# H1DR11.net
KiCad netlist of a schematic drawn in EAGLE
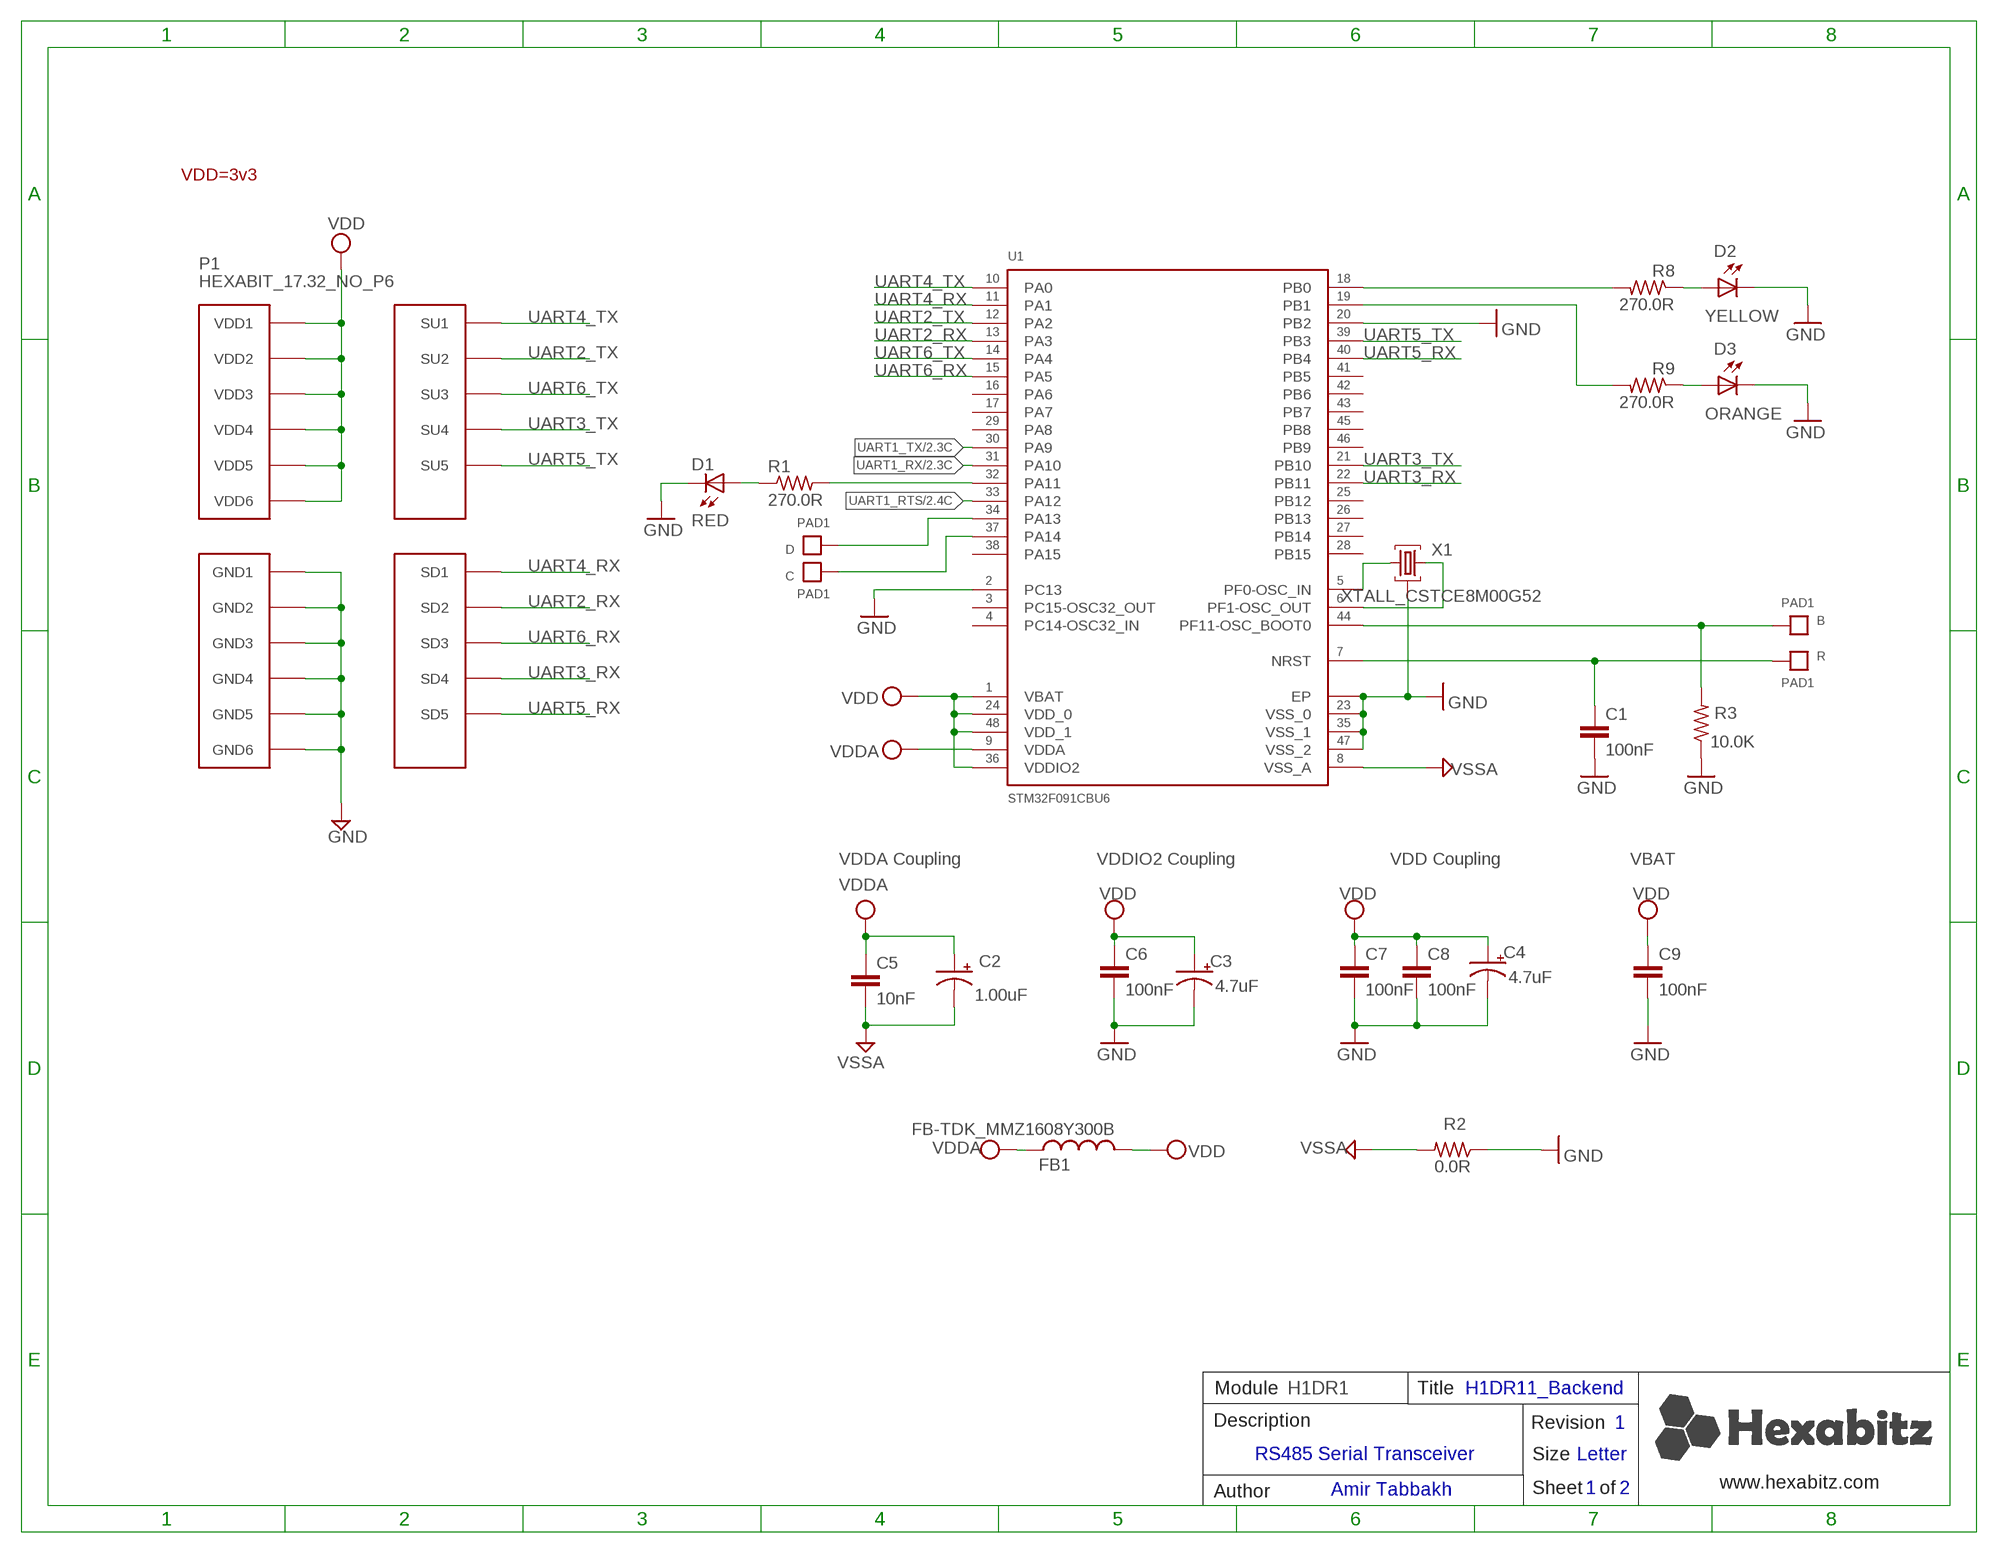
[diagram p0: schematic, sheet 1]
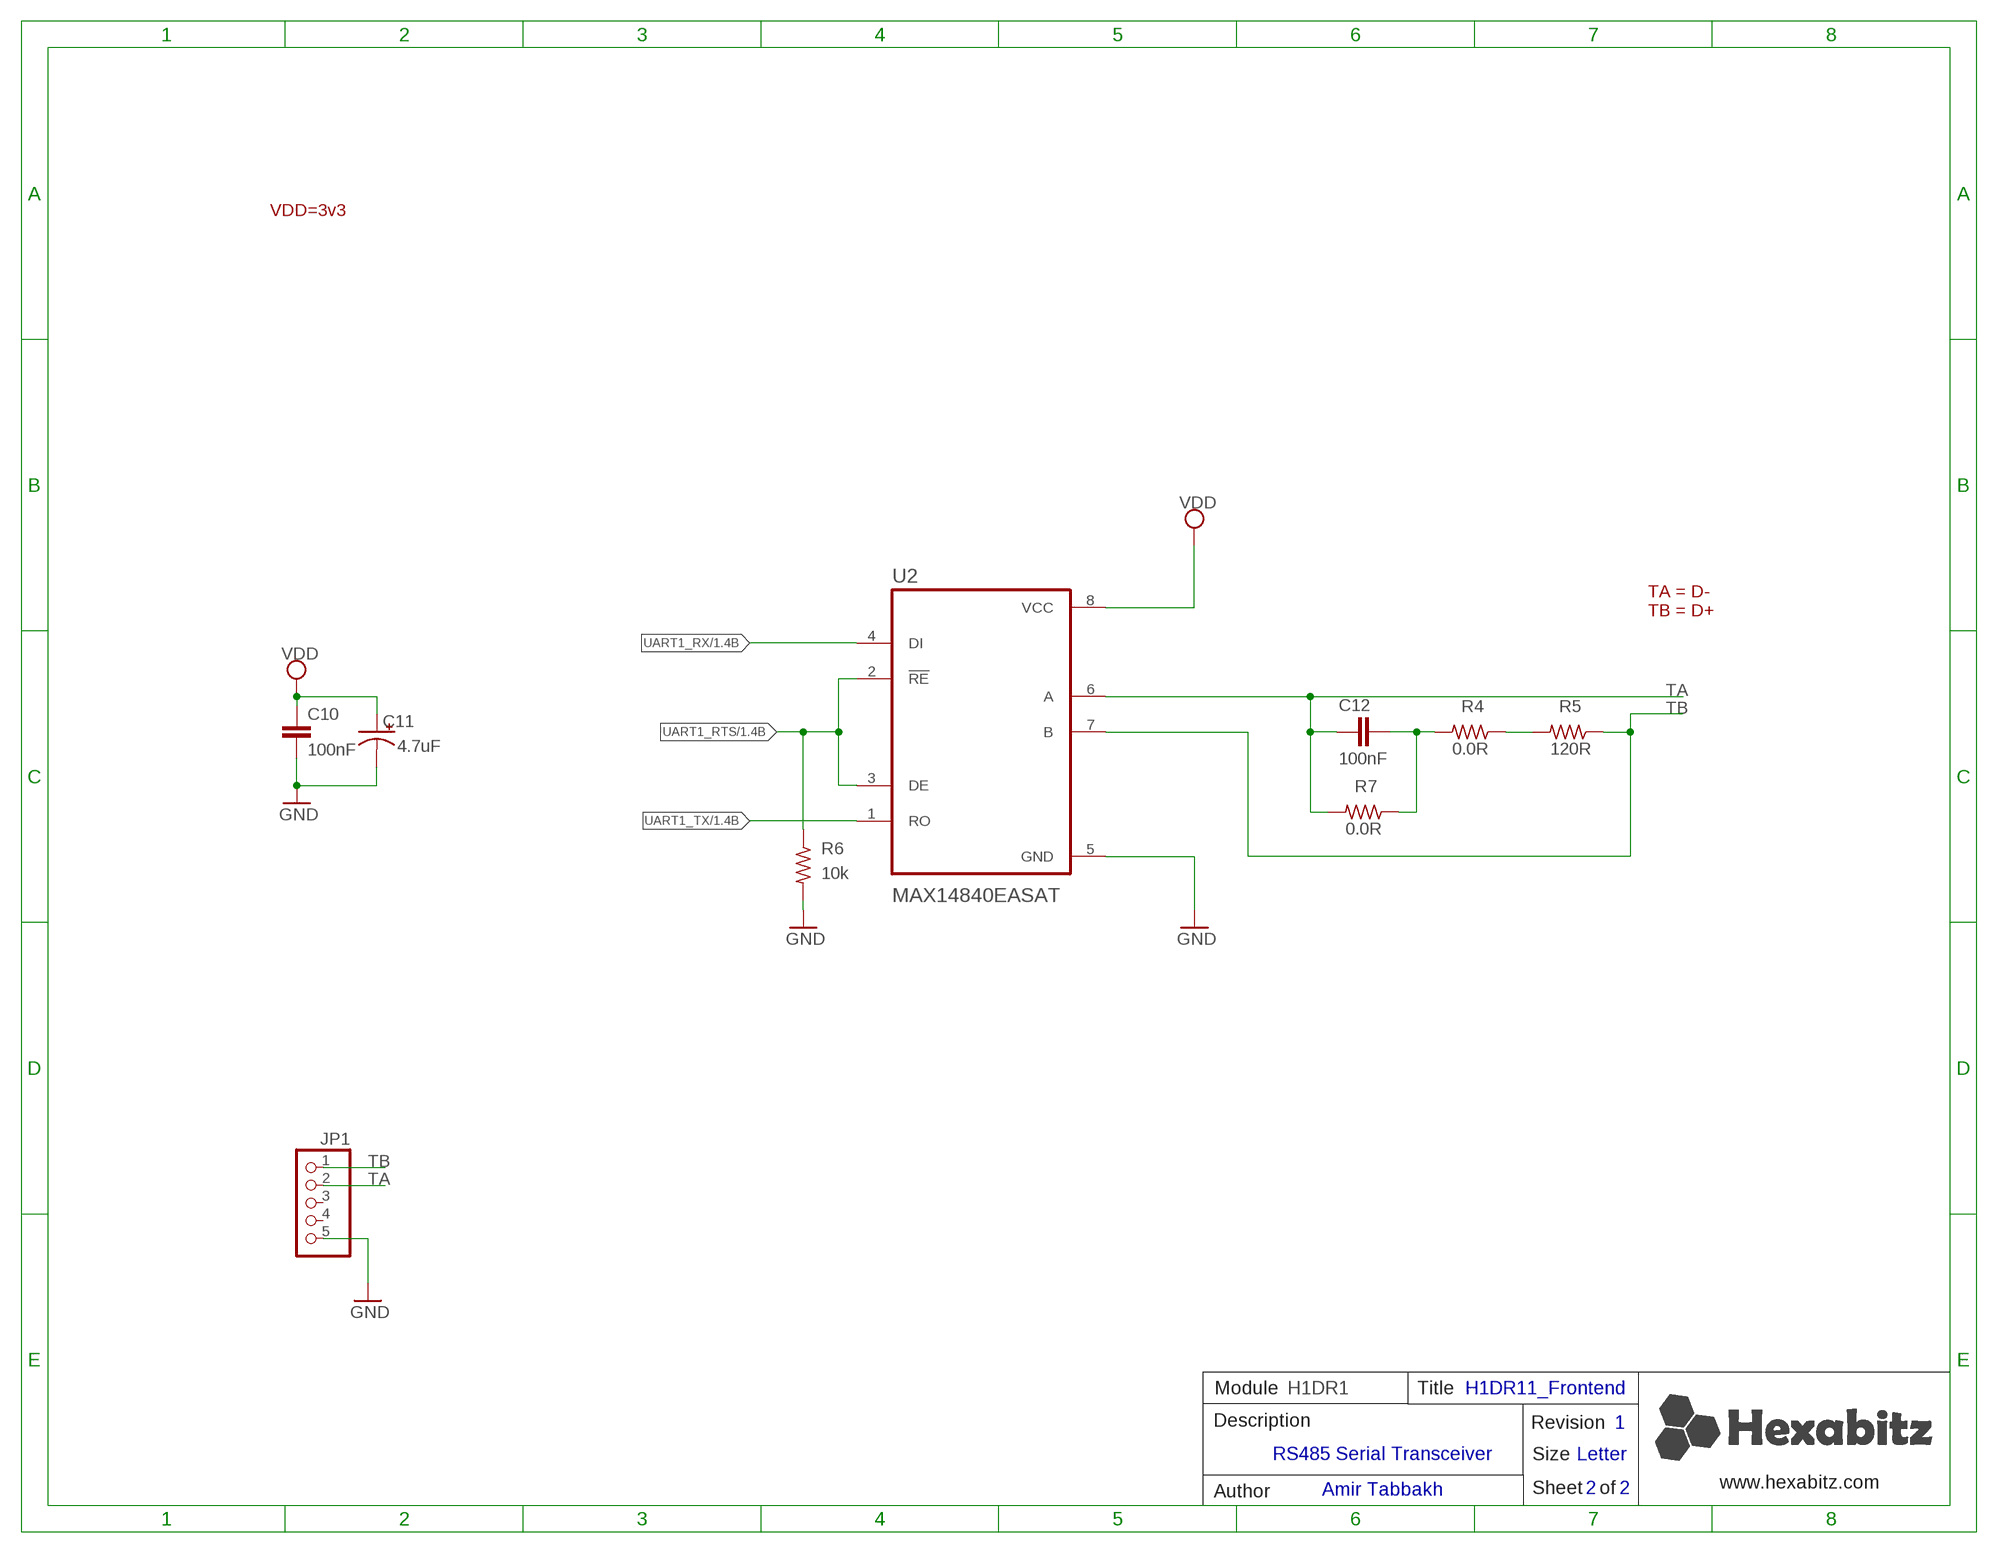
[diagram p1: schematic, sheet 2]

(export (version "E")
  (design (tool "Eeschema 10.0.6"))
  (components
    (comp (ref "C10")
      (value "100nF")
      (footprint "eagle-import:C-0603")
      (fields
        (field (name "CAPACITANCE") "100nF")
        (field (name "MFN") "KEMET")
        (field (name "MPN") "C0603C104K8RACTU")
        (field (name "OCTOPART_URL") "https://octopart.com/c0603c104k8ractu-kemet-145075?r=sp&s=9bS9ASSwSEqMCE9KBEQZ0g")
        (field (name "TOLERANCE") "10%")
        (field (name "VOLTAGE_RATING") "10V")
      )
      (libsource (lib "eagle-import") (part "C-0603"))
    )
    (comp (ref "C11")
      (value "4.7uF")
      (footprint "eagle-import:C-0805-POL")
      (fields
        (field (name "CAPACITANCE") "4.7uF")
        (field (name "MFN") "Murata")
        (field (name "MPN") "GRM21BC81E475KA12L")
        (field (name "OCTOPART_URL") "https://octopart.com/grm21bc81e475ka12l-murata-10331911?r=sp&s=RY3qZSD8T6mG6TC9CHI5qQ")
        (field (name "TOLERANCE") "10%")
        (field (name "VOLTAGE_RATING") "25V")
      )
      (libsource (lib "eagle-import") (part "C-0805-POL"))
    )
    (comp (ref "C12")
      (value "100nF")
      (footprint "eagle-import:C-0603")
      (fields
        (field (name "CAPACITANCE") "100nF")
        (field (name "MFN") "AVX")
        (field (name "MPN") "0603YC104K4T2A")
        (field (name "OCTOPART_URL") "https://octopart.com/0603yc104k4t2a-avx+interconnect+%2F+elco-8120651")
        (field (name "TOLERANCE") "10%")
        (field (name "VOLTAGE_RATING") "16V")
      )
      (libsource (lib "eagle-import") (part "C-0603"))
    )
    (comp (ref "JP1")
      (value "PINHD-1X5/90")
      (footprint "eagle-import:1X05_90")
      (description "Conn Header R/a 5POS 2.54MM MALE")
      (fields (field (name "MPN") "PEC05SBAN"))
      (libsource (lib "eagle-import") (part "PINHD-1X5/90"))
    )
    (comp (ref "R4")
      (value "0.0R")
      (footprint "eagle-import:R-0603")
      (fields
        (field (name "MFN") "Vishay")
        (field (name "MPN") "DNP")
        (field (name "OCTOPART_URL") "https://octopart.com/crcw06030000z0ea-vishay-39556096#")
        (field (name "RESISTANCE") "DNP")
      )
      (libsource (lib "eagle-import") (part "R-0603"))
    )
    (comp (ref "R5")
      (value "120R")
      (footprint "eagle-import:R-0805")
      (fields
        (field (name "MFN") "Panasonic")
        (field (name "MPN") "ERJP6WF1200V")
        (field (name "OCTOPART_URL") "https://octopart.com/erjp6wf1200v-panasonic-25949195?r=sp#")
        (field (name "RESISTANCE") "120R")
        (field (name "TOLERANCE") "1%")
      )
      (libsource (lib "eagle-import") (part "R-0805"))
    )
    (comp (ref "R6")
      (value "10k")
      (footprint "eagle-import:R-0603")
      (fields
        (field (name "MFN") "Vishay")
        (field (name "MPN") "CRCW060310K0JNEB")
        (field (name "OCTOPART_URL") "https://octopart.com/crcw060310k0jneb-vishay+dale-46603268")
        (field (name "RESISTANCE") "10k")
        (field (name "TOLERANCE") "5%")
      )
      (libsource (lib "eagle-import") (part "R-0603"))
    )
    (comp (ref "R7")
      (value "0.0R")
      (footprint "eagle-import:R-0603")
      (fields
        (field (name "MFN") "Vishay")
        (field (name "MPN") "CRCW06030000Z0EA")
        (field (name "OCTOPART_URL") "https://octopart.com/crcw06030000z0ea-vishay-39556096#")
        (field (name "RESISTANCE") "0.0 Ohm")
      )
      (libsource (lib "eagle-import") (part "R-0603"))
    )
    (comp (ref "U2")
      (value "MAX14840EASAT")
      (footprint "eagle-import:SOIC127P600X175-8N")
      (fields (field (name "MPN") "MAX14840EASA+"))
      (libsource (lib "eagle-import") (part "MAX14840EASAT"))
    )
    (comp (ref "B")
      (value "PAD1")
      (footprint "eagle-import:PAD1")
      (libsource (lib "eagle-import") (part "PAD1"))
    )
    (comp (ref "C")
      (value "PAD1")
      (footprint "eagle-import:PAD1")
      (libsource (lib "eagle-import") (part "PAD1"))
    )
    (comp (ref "C1")
      (value "100nF")
      (footprint "eagle-import:C-0603")
      (fields
        (field (name "CAPACITANCE") "100nF")
        (field (name "MFN") "KEMET")
        (field (name "MPN") "C0603C104K8RACTU")
        (field (name "OCTOPART_URL") "https://octopart.com/c0603c104k8ractu-kemet-145075?r=sp&s=9bS9ASSwSEqMCE9KBEQZ0g")
        (field (name "TOLERANCE") "10%")
        (field (name "VOLTAGE_RATING") "10V")
      )
      (libsource (lib "eagle-import") (part "C-0603"))
    )
    (comp (ref "C2")
      (value "1.00uF")
      (footprint "eagle-import:C-0805-POL")
      (fields
        (field (name "CAPACITANCE") "1.00uF")
        (field (name "MFN") "Yageo")
        (field (name "MPN") "CC0805KKX7R7BB105")
        (field (name "OCTOPART_URL") "https://octopart.com/cc0805kkx7r7bb105-yageo-8376555?r=sp&s=YKl1wwtkROau_X5nniH2ig")
        (field (name "TOLERANCE") "10%")
        (field (name "VOLTAGE_RATING") "16V")
      )
      (libsource (lib "eagle-import") (part "C-0805-POL"))
    )
    (comp (ref "C3")
      (value "4.7uF")
      (footprint "eagle-import:C-0805-POL")
      (fields
        (field (name "CAPACITANCE") "4.7uF")
        (field (name "MFN") "Murata")
        (field (name "MPN") "GRM21BC81E475KA12L")
        (field (name "OCTOPART_URL") "https://octopart.com/grm21bc81e475ka12l-murata-10331911?r=sp&s=RY3qZSD8T6mG6TC9CHI5qQ")
        (field (name "TOLERANCE") "10%")
        (field (name "VOLTAGE_RATING") "25V")
      )
      (libsource (lib "eagle-import") (part "C-0805-POL"))
    )
    (comp (ref "C4")
      (value "4.7uF")
      (footprint "eagle-import:C-0805-POL")
      (fields
        (field (name "CAPACITANCE") "4.7uF")
        (field (name "MFN") "Murata")
        (field (name "MPN") "GRM21BC81E475KA12L")
        (field (name "OCTOPART_URL") "https://octopart.com/grm21bc81e475ka12l-murata-10331911?r=sp&s=RY3qZSD8T6mG6TC9CHI5qQ")
        (field (name "TOLERANCE") "10%")
        (field (name "VOLTAGE_RATING") "25V")
      )
      (libsource (lib "eagle-import") (part "C-0805-POL"))
    )
    (comp (ref "C5")
      (value "10nF")
      (footprint "eagle-import:C-0603")
      (fields
        (field (name "CAPACITANCE") "10nF")
        (field (name "MFN") "KEMET")
        (field (name "MPN") "C0603C103K5RACTU")
        (field (name "OCTOPART_URL") "https://octopart.com/c0603c103k5ractu-kemet-133094?r=sp&s=R_iPBxLnSmGqhkU2rIMFpg")
        (field (name "TOLERANCE") "10%")
        (field (name "VOLTAGE_RATING") "50V")
      )
      (libsource (lib "eagle-import") (part "C-0603"))
    )
    (comp (ref "C6")
      (value "100nF")
      (footprint "eagle-import:C-0603")
      (fields
        (field (name "CAPACITANCE") "100nF")
        (field (name "MFN") "KEMET")
        (field (name "MPN") "C0603C104K8RACTU")
        (field (name "OCTOPART_URL") "https://octopart.com/c0603c104k8ractu-kemet-145075?r=sp&s=9bS9ASSwSEqMCE9KBEQZ0g")
        (field (name "TOLERANCE") "10%")
        (field (name "VOLTAGE_RATING") "10V")
      )
      (libsource (lib "eagle-import") (part "C-0603"))
    )
    (comp (ref "C7")
      (value "100nF")
      (footprint "eagle-import:C-0603")
      (fields
        (field (name "CAPACITANCE") "100nF")
        (field (name "MFN") "KEMET")
        (field (name "MPN") "C0603C104K8RACTU")
        (field (name "OCTOPART_URL") "https://octopart.com/c0603c104k8ractu-kemet-145075?r=sp&s=9bS9ASSwSEqMCE9KBEQZ0g")
        (field (name "TOLERANCE") "10%")
        (field (name "VOLTAGE_RATING") "10")
      )
      (libsource (lib "eagle-import") (part "C-0603"))
    )
    (comp (ref "C8")
      (value "100nF")
      (footprint "eagle-import:C-0603")
      (fields
        (field (name "CAPACITANCE") "100nF")
        (field (name "MFN") "KEMET")
        (field (name "MPN") "C0603C104K8RACTU")
        (field (name "OCTOPART_URL") "https://octopart.com/c0603c104k8ractu-kemet-145075?r=sp&s=9bS9ASSwSEqMCE9KBEQZ0g")
        (field (name "TOLERANCE") "10%")
        (field (name "VOLTAGE_RATING") "10V")
      )
      (libsource (lib "eagle-import") (part "C-0603"))
    )
    (comp (ref "C9")
      (value "100nF")
      (footprint "eagle-import:C-0603")
      (fields
        (field (name "CAPACITANCE") "100nF")
        (field (name "MFN") "KEMET")
        (field (name "MPN") "C0603C104K8RACTU")
        (field (name "OCTOPART_URL") "https://octopart.com/c0603c104k8ractu-kemet-145075?r=sp&s=9bS9ASSwSEqMCE9KBEQZ0g")
        (field (name "TOLERANCE") "10V")
        (field (name "VOLTAGE_RATING") "10%")
      )
      (libsource (lib "eagle-import") (part "C-0603"))
    )
    (comp (ref "D")
      (value "PAD1")
      (footprint "eagle-import:PAD1")
      (libsource (lib "eagle-import") (part "PAD1"))
    )
    (comp (ref "D1")
      (value "RED")
      (footprint "eagle-import:VLMS1300-GS08")
      (fields
        (field (name "MPN") "VLMS1300-GS08")
        (field (name "MFN") "Vishay")
        (field (name "MPN_1") "VLMS1300-GS08")
        (field (name "OCTOPART_URL") "https://octopart.com/vlms1300-gs08-vishay-21709201?r=sp&s=_gcP4_q8T1SC6PJQPTQ9yA")
      )
      (libsource (lib "eagle-import") (part "VLMS1300-GS08"))
    )
    (comp (ref "D2")
      (value "YELLOW")
      (footprint "eagle-import:VLMS1300-GS08")
      (fields
        (field (name "MPN") "VLMS1300-GS08")
        (field (name "MFN") "Vishay")
        (field (name "MPN_1") "VLMY1300-GS08")
        (field (name "OCTOPART_URL") "https://octopart.com/vlmy1300-gs08-vishay-21709204?r=sp")
      )
      (libsource (lib "eagle-import") (part "VLMS1300-GS08"))
    )
    (comp (ref "D3")
      (value "ORANGE")
      (footprint "eagle-import:VLMS1300-GS08")
      (fields
        (field (name "MPN") "VLMS1300-GS08")
        (field (name "MFN") "Vishay")
        (field (name "MPN_1") "VLMO1300-GS08 ")
        (field (name "OCTOPART_URL") "https://octopart.com/vlmo1300-gs08-vishay-21709200?r=sp#")
      )
      (libsource (lib "eagle-import") (part "VLMS1300-GS08"))
    )
    (comp (ref "FB1")
      (value "FB-TDK_MMZ1608Y300B")
      (footprint "eagle-import:FB-TDK_MMZ1608Y300B")
      (fields
        (field (name "MFN") "TDK ")
        (field (name "MPN") "MMZ1608Y300B")
        (field (name "OCTOPART_URL") "https://octopart.com/mmz1608y300b-tdk-368280?r=sp&s=cd9_2ZEqQ9q9UNBuQgHAiA")
      )
      (libsource (lib "eagle-import") (part "FB-TDK_MMZ1608Y300B"))
    )
    (comp (ref "P1")
      (value "HEXABIT_17.32_NO_P6")
      (footprint "eagle-import:HEXABIT_17.32_NO_P6")
      (libsource (lib "eagle-import") (part "HEXABIT_?_NO_P617.32"))
    )
    (comp (ref "R")
      (value "PAD1")
      (footprint "eagle-import:PAD1")
      (libsource (lib "eagle-import") (part "PAD1"))
    )
    (comp (ref "R1")
      (value "270.0R")
      (footprint "eagle-import:R-0603")
      (fields
        (field (name "MFN") "Yageo")
        (field (name "MPN") "RC0603FR-07270RL")
        (field (name "OCTOPART_URL") "https://octopart.com/search?q=RC0603FR-07270RL&start=0")
        (field (name "RESISTANCE") "270.0 Ohm")
        (field (name "TOLERANCE") "1%")
      )
      (libsource (lib "eagle-import") (part "R-0603"))
    )
    (comp (ref "R2")
      (value "0.0R")
      (footprint "eagle-import:R-0603")
      (fields
        (field (name "MFN") "Yageo")
        (field (name "MPN") "RC0603JR-070RL")
        (field (name "OCTOPART_URL") "https://octopart.com/rc0603jr-070rl-yageo-1241539?r=sp&s=X2NteqRjRNWrnx42Y0aliA")
        (field (name "RESISTANCE") "0.0 Ohm")
      )
      (libsource (lib "eagle-import") (part "R-0603"))
    )
    (comp (ref "R3")
      (value "10.0K")
      (footprint "eagle-import:R-0603")
      (fields
        (field (name "MFN") "Yageo")
        (field (name "MPN") "RC0603JR-0710KL")
        (field (name "OCTOPART_URL") "https://octopart.com/search?q=RC0603JR-0710KL&start=0")
        (field (name "RESISTANCE") "10.0K Ohm")
        (field (name "TOLERANCE") "5%")
      )
      (libsource (lib "eagle-import") (part "R-0603"))
    )
    (comp (ref "R8")
      (value "270.0R")
      (footprint "eagle-import:R-0603")
      (fields
        (field (name "MFN") "Yageo")
        (field (name "MPN") "RC0603FR-07270RL")
        (field (name "OCTOPART_URL") "https://octopart.com/search?q=RC0603FR-07270RL&start=0")
        (field (name "RESISTANCE") "270.0 Ohm")
        (field (name "TOLERANCE") "1%")
      )
      (libsource (lib "eagle-import") (part "R-0603"))
    )
    (comp (ref "R9")
      (value "270.0R")
      (footprint "eagle-import:R-0603")
      (fields
        (field (name "MFN") "Yageo")
        (field (name "MPN") "RC0603FR-07270RL")
        (field (name "OCTOPART_URL") "https://octopart.com/search?q=RC0603FR-07270RL&start=0")
        (field (name "RESISTANCE") "270.0 Ohm")
        (field (name "TOLERANCE") "1%")
      )
      (libsource (lib "eagle-import") (part "R-0603"))
    )
    (comp (ref "U1")
      (value "STM32F091CBU6")
      (footprint "eagle-import:STM32F091CBU6")
      (libsource (lib "eagle-import") (part "STM32F091CBU6"))
    )
    (comp (ref "X1")
      (value "XTALL_CSTCE8M00G52")
      (footprint "eagle-import:XTALL_CSTCE8M00G52")
      (fields (field (name "MPN") "CSTCE8M00G52Z-R0"))
      (libsource (lib "eagle-import") (part "XTALL_CSTCE8M00G52"))
    )
  )
  (nets
    (net (code "1") (name "GND") (class "Default")
      (node (ref "C1") (pin "2") (pinfunction "2_2") (pintype "passive"))
      (node (ref "C10") (pin "2") (pinfunction "2_2") (pintype "passive"))
      (node (ref "C11") (pin "2") (pinfunction "-_2") (pintype "passive"))
      (node (ref "C3") (pin "2") (pinfunction "-_2") (pintype "passive"))
      (node (ref "C4") (pin "2") (pinfunction "-_2") (pintype "passive"))
      (node (ref "C6") (pin "2") (pinfunction "2_2") (pintype "passive"))
      (node (ref "C7") (pin "2") (pinfunction "2_2") (pintype "passive"))
      (node (ref "C8") (pin "2") (pinfunction "2_2") (pintype "passive"))
      (node (ref "C9") (pin "2") (pinfunction "2_2") (pintype "passive"))
      (node (ref "D1") (pin "C") (pinfunction "C_C") (pintype "passive"))
      (node (ref "D2") (pin "C") (pinfunction "C_C") (pintype "passive"))
      (node (ref "D3") (pin "C") (pinfunction "C_C") (pintype "passive"))
      (node (ref "JP1") (pin "5") (pinfunction "5_5") (pintype "passive"))
      (node (ref "P1") (pin "PAD_PD10") (pinfunction "GND4_PAD_PD10") (pintype "power_in"))
      (node (ref "P1") (pin "PAD_PD11") (pinfunction "GND5_PAD_PD11") (pintype "power_in"))
      (node (ref "P1") (pin "PAD_PD12") (pinfunction "GND6_PAD_PD12") (pintype "power_in"))
      (node (ref "P1") (pin "PAD_PD7") (pinfunction "GND1_PAD_PD7") (pintype "power_in"))
      (node (ref "P1") (pin "PAD_PD8") (pinfunction "GND2_PAD_PD8") (pintype "power_in"))
      (node (ref "P1") (pin "PAD_PD9") (pinfunction "GND3_PAD_PD9") (pintype "power_in"))
      (node (ref "R2") (pin "1") (pinfunction "1_1") (pintype "passive"))
      (node (ref "R3") (pin "1") (pinfunction "1_1") (pintype "passive"))
      (node (ref "R6") (pin "2") (pinfunction "2_2") (pintype "passive"))
      (node (ref "U1") (pin "EP") (pinfunction "EP_EP") (pintype "power_in"))
      (node (ref "U1") (pin "P$2") (pinfunction "PC13_P$2") (pintype "bidirectional"))
      (node (ref "U1") (pin "P$20") (pinfunction "PB2_P$20") (pintype "bidirectional"))
      (node (ref "U1") (pin "P$23") (pinfunction "VSS_0_P$23") (pintype "power_in"))
      (node (ref "U1") (pin "P$35") (pinfunction "VSS_1_P$35") (pintype "power_in"))
      (node (ref "U1") (pin "P$47") (pinfunction "VSS_2_P$47") (pintype "power_in"))
      (node (ref "U2") (pin "5") (pinfunction "GND_5") (pintype "power_in"))
      (node (ref "X1") (pin "P$2") (pinfunction "2_P$2") (pintype "passive"))
    )
    (net (code "2") (name "Net-(C12-Pad2)") (class "Default")
      (node (ref "C12") (pin "2") (pinfunction "2_2") (pintype "passive"))
      (node (ref "R4") (pin "2") (pinfunction "2_2") (pintype "passive"))
      (node (ref "R7") (pin "1") (pinfunction "1_1") (pintype "passive"))
    )
    (net (code "3") (name "Net-(D1-PadA)") (class "Default")
      (node (ref "D1") (pin "A") (pinfunction "A_A") (pintype "passive"))
      (node (ref "R1") (pin "1") (pinfunction "1_1") (pintype "passive"))
    )
    (net (code "4") (name "Net-(D2-PadA)") (class "Default")
      (node (ref "D2") (pin "A") (pinfunction "A_A") (pintype "passive"))
      (node (ref "R8") (pin "1") (pinfunction "1_1") (pintype "passive"))
    )
    (net (code "5") (name "Net-(D3-PadA)") (class "Default")
      (node (ref "D3") (pin "A") (pinfunction "A_A") (pintype "passive"))
      (node (ref "R9") (pin "1") (pinfunction "1_1") (pintype "passive"))
    )
    (net (code "6") (name "Net-(R4-Pad1)") (class "Default")
      (node (ref "R4") (pin "1") (pinfunction "1_1") (pintype "passive"))
      (node (ref "R5") (pin "2") (pinfunction "2_2") (pintype "passive"))
    )
    (net (code "7") (name "Net-(U1-NRST)") (class "Default")
      (node (ref "C1") (pin "1") (pinfunction "1_1") (pintype "passive"))
      (node (ref "R") (pin "P$1") (pinfunction "P$1_P$1") (pintype "passive"))
      (node (ref "R") (pin "P$2") (pinfunction "P$1_P$2") (pintype "passive"))
      (node (ref "U1") (pin "P$7") (pinfunction "NRST_P$7") (pintype "passive"))
    )
    (net (code "8") (name "Net-(U1-PA11)") (class "Default")
      (node (ref "R1") (pin "2") (pinfunction "2_2") (pintype "passive"))
      (node (ref "U1") (pin "P$32") (pinfunction "PA11_P$32") (pintype "bidirectional"))
    )
    (net (code "9") (name "Net-(U1-PA13)") (class "Default")
      (node (ref "D") (pin "P$1") (pinfunction "P$1_P$1") (pintype "passive"))
      (node (ref "D") (pin "P$2") (pinfunction "P$1_P$2") (pintype "passive"))
      (node (ref "U1") (pin "P$34") (pinfunction "PA13_P$34") (pintype "bidirectional"))
    )
    (net (code "10") (name "Net-(U1-PA14)") (class "Default")
      (node (ref "C") (pin "P$1") (pinfunction "P$1_P$1") (pintype "passive"))
      (node (ref "C") (pin "P$2") (pinfunction "P$1_P$2") (pintype "passive"))
      (node (ref "U1") (pin "P$37") (pinfunction "PA14_P$37") (pintype "bidirectional"))
    )
    (net (code "11") (name "Net-(U1-PB0)") (class "Default")
      (node (ref "R8") (pin "2") (pinfunction "2_2") (pintype "passive"))
      (node (ref "U1") (pin "P$18") (pinfunction "PB0_P$18") (pintype "bidirectional"))
    )
    (net (code "12") (name "Net-(U1-PB1)") (class "Default")
      (node (ref "R9") (pin "2") (pinfunction "2_2") (pintype "passive"))
      (node (ref "U1") (pin "P$19") (pinfunction "PB1_P$19") (pintype "bidirectional"))
    )
    (net (code "13") (name "Net-(U1-PF0-OSC_IN)") (class "Default")
      (node (ref "U1") (pin "P$5") (pinfunction "PF0-OSC_IN_P$5") (pintype "bidirectional"))
      (node (ref "X1") (pin "P$1") (pinfunction "1_P$1") (pintype "passive"))
    )
    (net (code "14") (name "Net-(U1-PF1-OSC_OUT)") (class "Default")
      (node (ref "U1") (pin "P$6") (pinfunction "PF1-OSC_OUT_P$6") (pintype "bidirectional"))
      (node (ref "X1") (pin "P$3") (pinfunction "3_P$3") (pintype "passive"))
    )
    (net (code "15") (name "Net-(U1-PF11-OSC_BOOT0)") (class "Default")
      (node (ref "B") (pin "P$1") (pinfunction "P$1_P$1") (pintype "passive"))
      (node (ref "B") (pin "P$2") (pinfunction "P$1_P$2") (pintype "passive"))
      (node (ref "R3") (pin "2") (pinfunction "2_2") (pintype "passive"))
      (node (ref "U1") (pin "P$44") (pinfunction "PF11-OSC_BOOT0_P$44") (pintype "bidirectional"))
    )
    (net (code "16") (name "TA") (class "Default")
      (node (ref "C12") (pin "1") (pinfunction "1_1") (pintype "passive"))
      (node (ref "JP1") (pin "2") (pinfunction "2_2") (pintype "passive"))
      (node (ref "R7") (pin "2") (pinfunction "2_2") (pintype "passive"))
      (node (ref "U2") (pin "6") (pinfunction "A_6") (pintype "bidirectional"))
    )
    (net (code "17") (name "TB") (class "Default")
      (node (ref "JP1") (pin "1") (pinfunction "1_1") (pintype "passive"))
      (node (ref "R5") (pin "1") (pinfunction "1_1") (pintype "passive"))
      (node (ref "U2") (pin "7") (pinfunction "B_7") (pintype "bidirectional"))
    )
    (net (code "18") (name "UART1_RTS") (class "Default")
      (node (ref "R6") (pin "1") (pinfunction "1_1") (pintype "passive"))
      (node (ref "U1") (pin "P$33") (pinfunction "PA12_P$33") (pintype "bidirectional"))
      (node (ref "U2") (pin "2") (pinfunction "~{RE}_2") (pintype "bidirectional"))
      (node (ref "U2") (pin "3") (pinfunction "DE_3") (pintype "bidirectional"))
    )
    (net (code "19") (name "UART1_RX") (class "Default")
      (node (ref "U1") (pin "P$31") (pinfunction "PA10_P$31") (pintype "bidirectional"))
      (node (ref "U2") (pin "4") (pinfunction "DI_4") (pintype "input"))
    )
    (net (code "20") (name "UART1_TX") (class "Default")
      (node (ref "U1") (pin "P$30") (pinfunction "PA9_P$30") (pintype "bidirectional"))
      (node (ref "U2") (pin "1") (pinfunction "RO_1") (pintype "bidirectional"))
    )
    (net (code "21") (name "UART2_RX") (class "Default")
      (node (ref "P1") (pin "PAD_PD2") (pinfunction "SD2_PAD_PD2") (pintype "bidirectional"))
      (node (ref "U1") (pin "P$13") (pinfunction "PA3_P$13") (pintype "bidirectional"))
    )
    (net (code "22") (name "UART2_TX") (class "Default")
      (node (ref "P1") (pin "PAD_PU2") (pinfunction "SU2_PAD_PU2") (pintype "bidirectional"))
      (node (ref "U1") (pin "P$12") (pinfunction "PA2_P$12") (pintype "bidirectional"))
    )
    (net (code "23") (name "UART3_RX") (class "Default")
      (node (ref "P1") (pin "PAD_PD4") (pinfunction "SD4_PAD_PD4") (pintype "bidirectional"))
      (node (ref "U1") (pin "P$22") (pinfunction "PB11_P$22") (pintype "bidirectional"))
    )
    (net (code "24") (name "UART3_TX") (class "Default")
      (node (ref "P1") (pin "PAD_PU4") (pinfunction "SU4_PAD_PU4") (pintype "bidirectional"))
      (node (ref "U1") (pin "P$21") (pinfunction "PB10_P$21") (pintype "bidirectional"))
    )
    (net (code "25") (name "UART4_RX") (class "Default")
      (node (ref "P1") (pin "PAD_PD1") (pinfunction "SD1_PAD_PD1") (pintype "bidirectional"))
      (node (ref "U1") (pin "P$11") (pinfunction "PA1_P$11") (pintype "bidirectional"))
    )
    (net (code "26") (name "UART4_TX") (class "Default")
      (node (ref "P1") (pin "PAD_PU1") (pinfunction "SU1_PAD_PU1") (pintype "bidirectional"))
      (node (ref "U1") (pin "P$10") (pinfunction "PA0_P$10") (pintype "bidirectional"))
    )
    (net (code "27") (name "UART5_RX") (class "Default")
      (node (ref "P1") (pin "PAD_PD5") (pinfunction "SD5_PAD_PD5") (pintype "bidirectional"))
      (node (ref "U1") (pin "P$40") (pinfunction "PB4_P$40") (pintype "bidirectional"))
    )
    (net (code "28") (name "UART5_TX") (class "Default")
      (node (ref "P1") (pin "PAD_PU5") (pinfunction "SU5_PAD_PU5") (pintype "bidirectional"))
      (node (ref "U1") (pin "P$39") (pinfunction "PB3_P$39") (pintype "bidirectional"))
    )
    (net (code "29") (name "UART6_RX") (class "Default")
      (node (ref "P1") (pin "PAD_PD3") (pinfunction "SD3_PAD_PD3") (pintype "bidirectional"))
      (node (ref "U1") (pin "P$15") (pinfunction "PA5_P$15") (pintype "bidirectional"))
    )
    (net (code "30") (name "UART6_TX") (class "Default")
      (node (ref "P1") (pin "PAD_PU3") (pinfunction "SU3_PAD_PU3") (pintype "bidirectional"))
      (node (ref "U1") (pin "P$14") (pinfunction "PA4_P$14") (pintype "bidirectional"))
    )
    (net (code "31") (name "VDD") (class "Default")
      (node (ref "C10") (pin "1") (pinfunction "1_1") (pintype "passive"))
      (node (ref "C11") (pin "1") (pinfunction "+_1") (pintype "passive"))
      (node (ref "C3") (pin "1") (pinfunction "+_1") (pintype "passive"))
      (node (ref "C4") (pin "1") (pinfunction "+_1") (pintype "passive"))
      (node (ref "C6") (pin "1") (pinfunction "1_1") (pintype "passive"))
      (node (ref "C7") (pin "1") (pinfunction "1_1") (pintype "passive"))
      (node (ref "C8") (pin "1") (pinfunction "1_1") (pintype "passive"))
      (node (ref "C9") (pin "1") (pinfunction "1_1") (pintype "passive"))
      (node (ref "FB1") (pin "2") (pinfunction "2_2") (pintype "passive"))
      (node (ref "P1") (pin "PAD_PU10") (pinfunction "VDD4_PAD_PU10") (pintype "power_in"))
      (node (ref "P1") (pin "PAD_PU11") (pinfunction "VDD5_PAD_PU11") (pintype "power_in"))
      (node (ref "P1") (pin "PAD_PU12") (pinfunction "VDD6_PAD_PU12") (pintype "power_in"))
      (node (ref "P1") (pin "PAD_PU7") (pinfunction "VDD1_PAD_PU7") (pintype "power_in"))
      (node (ref "P1") (pin "PAD_PU8") (pinfunction "VDD2_PAD_PU8") (pintype "power_in"))
      (node (ref "P1") (pin "PAD_PU9") (pinfunction "VDD3_PAD_PU9") (pintype "power_in"))
      (node (ref "U1") (pin "P$1") (pinfunction "VBAT_P$1") (pintype "power_in"))
      (node (ref "U1") (pin "P$24") (pinfunction "VDD_0_P$24") (pintype "power_in"))
      (node (ref "U1") (pin "P$36") (pinfunction "VDDIO2_P$36") (pintype "power_in"))
      (node (ref "U1") (pin "P$48") (pinfunction "VDD_1_P$48") (pintype "power_in"))
      (node (ref "U2") (pin "8") (pinfunction "VCC_8") (pintype "power_in"))
    )
    (net (code "32") (name "VDDA") (class "Default")
      (node (ref "C2") (pin "1") (pinfunction "+_1") (pintype "passive"))
      (node (ref "C5") (pin "1") (pinfunction "1_1") (pintype "passive"))
      (node (ref "FB1") (pin "1") (pinfunction "1_1") (pintype "passive"))
      (node (ref "U1") (pin "P$9") (pinfunction "VDDA_P$9") (pintype "power_in"))
    )
    (net (code "33") (name "VSSA") (class "Default")
      (node (ref "C2") (pin "2") (pinfunction "-_2") (pintype "passive"))
      (node (ref "C5") (pin "2") (pinfunction "2_2") (pintype "passive"))
      (node (ref "R2") (pin "2") (pinfunction "2_2") (pintype "passive"))
      (node (ref "U1") (pin "P$8") (pinfunction "VSS_A_P$8") (pintype "power_in"))
    )
    (net (code "34") (name "unconnected-(JP1-Pad3)") (class "Default")
      (node (ref "JP1") (pin "3") (pinfunction "3_3") (pintype "passive"))
    )
    (net (code "35") (name "unconnected-(JP1-Pad4)") (class "Default")
      (node (ref "JP1") (pin "4") (pinfunction "4_4") (pintype "passive"))
    )
    (net (code "36") (name "unconnected-(U1-PA6-PadP$16)") (class "Default")
      (node (ref "U1") (pin "P$16") (pinfunction "PA6_P$16") (pintype "bidirectional"))
    )
    (net (code "37") (name "unconnected-(U1-PA7-PadP$17)") (class "Default")
      (node (ref "U1") (pin "P$17") (pinfunction "PA7_P$17") (pintype "bidirectional"))
    )
    (net (code "38") (name "unconnected-(U1-PA8-PadP$29)") (class "Default")
      (node (ref "U1") (pin "P$29") (pinfunction "PA8_P$29") (pintype "bidirectional"))
    )
    (net (code "39") (name "unconnected-(U1-PA15-PadP$38)") (class "Default")
      (node (ref "U1") (pin "P$38") (pinfunction "PA15_P$38") (pintype "bidirectional"))
    )
    (net (code "40") (name "unconnected-(U1-PB5-PadP$41)") (class "Default")
      (node (ref "U1") (pin "P$41") (pinfunction "PB5_P$41") (pintype "bidirectional"))
    )
    (net (code "41") (name "unconnected-(U1-PB6-PadP$42)") (class "Default")
      (node (ref "U1") (pin "P$42") (pinfunction "PB6_P$42") (pintype "bidirectional"))
    )
    (net (code "42") (name "unconnected-(U1-PB7-PadP$43)") (class "Default")
      (node (ref "U1") (pin "P$43") (pinfunction "PB7_P$43") (pintype "bidirectional"))
    )
    (net (code "43") (name "unconnected-(U1-PB8-PadP$45)") (class "Default")
      (node (ref "U1") (pin "P$45") (pinfunction "PB8_P$45") (pintype "bidirectional"))
    )
    (net (code "44") (name "unconnected-(U1-PB9-PadP$46)") (class "Default")
      (node (ref "U1") (pin "P$46") (pinfunction "PB9_P$46") (pintype "bidirectional"))
    )
    (net (code "45") (name "unconnected-(U1-PB12-PadP$25)") (class "Default")
      (node (ref "U1") (pin "P$25") (pinfunction "PB12_P$25") (pintype "bidirectional"))
    )
    (net (code "46") (name "unconnected-(U1-PB13-PadP$26)") (class "Default")
      (node (ref "U1") (pin "P$26") (pinfunction "PB13_P$26") (pintype "bidirectional"))
    )
    (net (code "47") (name "unconnected-(U1-PB14-PadP$27)") (class "Default")
      (node (ref "U1") (pin "P$27") (pinfunction "PB14_P$27") (pintype "bidirectional"))
    )
    (net (code "48") (name "unconnected-(U1-PB15-PadP$28)") (class "Default")
      (node (ref "U1") (pin "P$28") (pinfunction "PB15_P$28") (pintype "bidirectional"))
    )
    (net (code "49") (name "unconnected-(U1-PC14-OSC32_IN-PadP$3)") (class "Default")
      (node (ref "U1") (pin "P$3") (pinfunction "PC14-OSC32_IN_P$3") (pintype "bidirectional"))
    )
    (net (code "50") (name "unconnected-(U1-PC15-OSC32_OUT-PadP$4)") (class "Default")
      (node (ref "U1") (pin "P$4") (pinfunction "PC15-OSC32_OUT_P$4") (pintype "bidirectional"))
    )
  )
)
